# AFE_MCX_Adapter.net
KiCad netlist of a schematic drawn in Altium Designer
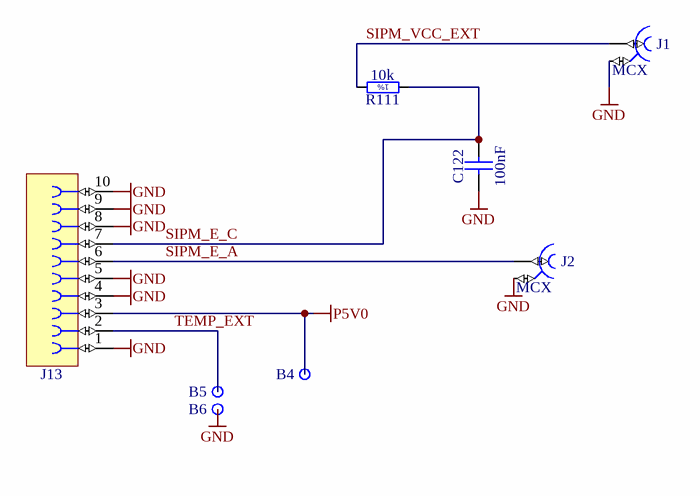
[diagram p0: AFE_MCX_Adapter.SchDoc]

(export (version "E")
  (design (tool "Eeschema 10.0.6"))
  (components
    (comp (ref "B4")
      (value "Plated Hole")
      (footprint "c130h80")
      (description "Single Terminal Socket")
      (fields (field (name "PART NUMBER") "PLATED_HOLE0.8_PAD1.3") (field (name "AUTHOR") "CERN DEM JLC"))
      (libsource (lib "Eletro-mechanical") (part "Single Terminal Socket"))
    )
    (comp (ref "B5")
      (value "Plated Hole")
      (footprint "c130h80")
      (description "Single Terminal Socket")
      (fields (field (name "PART NUMBER") "PLATED_HOLE0.8_PAD1.3") (field (name "AUTHOR") "CERN DEM JLC"))
      (libsource (lib "Eletro-mechanical") (part "Single Terminal Socket"))
    )
    (comp (ref "B6")
      (value "Plated Hole")
      (footprint "c130h80")
      (description "Single Terminal Socket")
      (fields (field (name "PART NUMBER") "PLATED_HOLE0.8_PAD1.3") (field (name "AUTHOR") "CERN DEM JLC"))
      (libsource (lib "Eletro-mechanical") (part "Single Terminal Socket"))
    )
    (comp (ref "C122")
      (value "100nF")
      (footprint "CAPC1608X90N")
      (description "Non-polarised capacitor")
      (fields
        (field (name "PART NUMBER") "CC0603_100NF_100V_10%_X7R")
        (field (name "VOLTAGE") "100V")
        (field (name "AUTHOR") "CERN DEM JLC")
      )
      (libsource (lib "Capacitors") (part "Capacitor - non polarized"))
    )
    (comp (ref "J1")
      (value "MCX")
      (footprint "AMPHENOL_919-383J-51A")
      (fields
        (field (name "PART NUMBER") "AMPHENOL_919-383J-51A")
        (field (name "MANUFACTURER") "AMPHENOL")
        (field (name "MANUFACTURER PART NUMBER") "919-383J-51A")
        (field (name "AUTHOR") "CERN DEM BC")
      )
      (libsource (lib "Connectors") (part "Coax_1Female_1Shield"))
    )
    (comp (ref "J2")
      (value "MCX")
      (footprint "AMPHENOL_919-383J-51A")
      (fields
        (field (name "PART NUMBER") "AMPHENOL_919-383J-51A")
        (field (name "MANUFACTURER") "AMPHENOL")
        (field (name "MANUFACTURER PART NUMBER") "919-383J-51A")
        (field (name "AUTHOR") "CERN DEM BC")
      )
      (libsource (lib "Connectors") (part "Coax_1Female_1Shield"))
    )
    (comp (ref "J13")
      (value "FFC/FPC")
      (footprint "MOLEX_52745-1097")
      (description "Connector 10 Female")
      (fields
        (field (name "PART NUMBER") "MOLEX_52745-1097")
        (field (name "MANUFACTURER") "MOLEX")
        (field (name "AUTHOR") "CERN DEM JLC")
      )
      (libsource (lib "Connectors") (part "Connector 10 Female"))
    )
    (comp (ref "R111")
      (value "10k")
      (footprint "RESC1005X40N")
      (description "Resistor - 1%")
      (fields
        (field (name "PART NUMBER") "R0402_10K_1%_0.0625W_100PPM")
        (field (name "POWER") "0.0625W")
        (field (name "AUTHOR") "CERN DEM JLC")
      )
      (libsource (lib "Resistors") (part "Resistor - 1%"))
    )
  )
  (nets
    (net (code "1") (name "/SIPM_E_A") (class "Default")
      (node (ref "J13") (pin "6") (pinfunction "6_6") (pintype "bidirectional"))
      (node (ref "J2") (pin "1") (pinfunction "1_1") (pintype "bidirectional"))
    )
    (net (code "2") (name "/SIPM_E_C") (class "Default")
      (node (ref "C122") (pin "2") (pinfunction "2_2") (pintype "passive"))
      (node (ref "J13") (pin "7") (pinfunction "7_7") (pintype "bidirectional"))
      (node (ref "R111") (pin "1") (pinfunction "1_1") (pintype "passive"))
    )
    (net (code "3") (name "/SIPM_VCC_EXT") (class "Default")
      (node (ref "J1") (pin "1") (pinfunction "1_1") (pintype "bidirectional"))
      (node (ref "R111") (pin "2") (pinfunction "2_2") (pintype "passive"))
    )
    (net (code "4") (name "/TEMP_EXT") (class "Default")
      (node (ref "B5") (pin "1") (pinfunction "1_1") (pintype "bidirectional"))
      (node (ref "J13") (pin "2") (pinfunction "2_2") (pintype "bidirectional"))
    )
    (net (code "5") (name "GND") (class "Default")
      (node (ref "B6") (pin "1") (pinfunction "1_1") (pintype "bidirectional"))
      (node (ref "C122") (pin "1") (pinfunction "1_1") (pintype "passive"))
      (node (ref "J1") (pin "2") (pinfunction "2_2") (pintype "bidirectional"))
      (node (ref "J13") (pin "1") (pinfunction "1_1") (pintype "bidirectional"))
      (node (ref "J13") (pin "10") (pinfunction "10_10") (pintype "bidirectional"))
      (node (ref "J13") (pin "4") (pinfunction "4_4") (pintype "bidirectional"))
      (node (ref "J13") (pin "5") (pinfunction "5_5") (pintype "bidirectional"))
      (node (ref "J13") (pin "8") (pinfunction "8_8") (pintype "bidirectional"))
      (node (ref "J13") (pin "9") (pinfunction "9_9") (pintype "bidirectional"))
      (node (ref "J2") (pin "2") (pinfunction "2_2") (pintype "bidirectional"))
    )
    (net (code "6") (name "P5V0") (class "Default")
      (node (ref "B4") (pin "1") (pinfunction "1_1") (pintype "bidirectional"))
      (node (ref "J13") (pin "3") (pinfunction "3_3") (pintype "bidirectional"))
    )
  )
)
